# Battery_Protection.net
KiCad netlist of a schematic drawn in Altium Designer
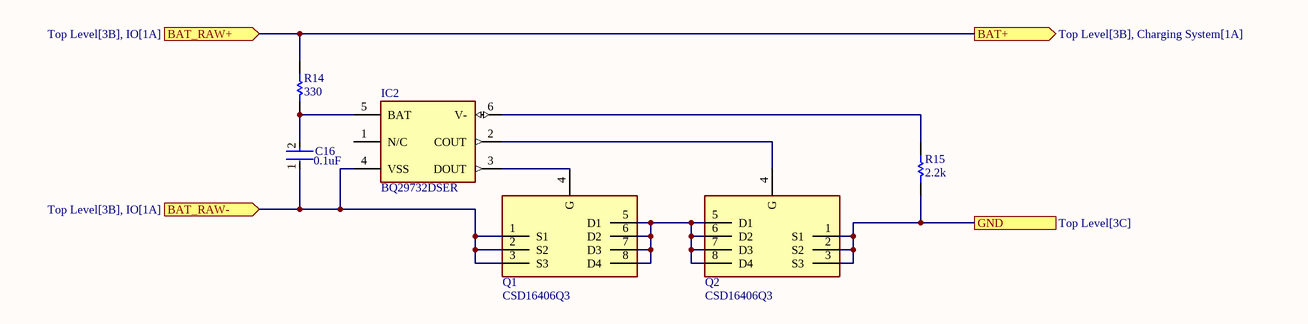
[diagram p0: Battery Protection.SchDoc]

(export (version "E")
  (design (tool "Eeschema 10.0.6"))
  (components
    (comp (ref "C16")
      (value "C1608X5R1A106K080AC")
      (footprint "FP-C1608-080-0_1-MFG")
      (description "Multilayer Ceramic Capacitors 10μF ±10% 10V X5R SMD 0603")
      (fields
        (field (name "VOLTAGE") "10V")
        (field (name "TOLERANCE") "10%")
        (field (name "CAPACITANCE") "0.1uF")
      )
      (libsource (lib "Altium Content Vault") (part "236180d848d6139a670b325ea6854c9"))
    )
    (comp (ref "IC2")
      (value "BQ29732DSER")
      (footprint "SON50P150X150X80-6N")
      (description "Integrated Circuit")
      (fields (field (name "MOUSER PART NUMBER") "595-BQ29732DSER"))
      (libsource (lib "Receiver_Library") (part "BQ29732DSER"))
    )
    (comp (ref "Q1")
      (value "CSD16406Q3")
      (footprint "DQG_VSON-CLIP")
      (description "MOSFET (N-Channel)")
      (fields (field (name "MOUSER PART NUMBER") "595-CSD16406Q3"))
      (libsource (lib "") (part "CSD16406Q3_1"))
    )
    (comp (ref "Q2")
      (value "CSD16406Q3")
      (footprint "DQG_VSON-CLIP")
      (description "MOSFET (N-Channel)")
      (fields (field (name "MOUSER PART NUMBER") "595-CSD16406Q3"))
      (libsource (lib "Receiver_Library") (part "CSD16406Q3"))
    )
    (comp (ref "R14")
      (value "330")
      (footprint "0603")
      (description "Thick Film Resistors - SMD 1/10Watt 2.1Kohms 1%")
      (fields (field (name "Comment") "CRCW06032K10FKEAC"))
      (libsource (lib "Receiver_Library") (part "CRCW06032K10FKEAC"))
    )
    (comp (ref "R15")
      (value "2.2k")
      (footprint "0603")
      (description "Thick Film Resistors - SMD 1/10Watt 2.1Kohms 1%")
      (fields (field (name "Comment") "CRCW06032K10FKEAC"))
      (libsource (lib "Receiver_Library") (part "CRCW06032K10FKEAC"))
    )
  )
  (nets
    (net (code "1") (name "/BAT+") (class "Default")
      (node (ref "R14") (pin "1") (pinfunction "1_1") (pintype "passive"))
    )
    (net (code "2") (name "/BAT_RAW-") (class "Default")
      (node (ref "C16") (pin "1") (pinfunction "1_1") (pintype "passive"))
      (node (ref "IC2") (pin "4") (pinfunction "VSS_4") (pintype "power_in"))
      (node (ref "Q1") (pin "1") (pinfunction "S1_1") (pintype "passive"))
      (node (ref "Q1") (pin "2") (pinfunction "S2_2") (pintype "passive"))
      (node (ref "Q1") (pin "3") (pinfunction "S3_3") (pintype "passive"))
    )
    (net (code "3") (name "/GND") (class "Default")
      (node (ref "Q2") (pin "1") (pinfunction "S1_1") (pintype "passive"))
      (node (ref "Q2") (pin "2") (pinfunction "S2_2") (pintype "passive"))
      (node (ref "Q2") (pin "3") (pinfunction "S3_3") (pintype "passive"))
      (node (ref "R15") (pin "2") (pinfunction "2_2") (pintype "passive"))
    )
    (net (code "4") (name "Net-(IC2-BAT)") (class "Default")
      (node (ref "C16") (pin "2") (pinfunction "2_2") (pintype "passive"))
      (node (ref "IC2") (pin "5") (pinfunction "BAT_5") (pintype "power_in"))
      (node (ref "R14") (pin "2") (pinfunction "2_2") (pintype "passive"))
    )
    (net (code "5") (name "Net-(IC2-COUT)") (class "Default")
      (node (ref "IC2") (pin "2") (pinfunction "COUT_2") (pintype "output"))
      (node (ref "Q2") (pin "4") (pinfunction "G_4") (pintype "passive"))
    )
    (net (code "6") (name "Net-(IC2-DOUT)") (class "Default")
      (node (ref "IC2") (pin "3") (pinfunction "DOUT_3") (pintype "output"))
      (node (ref "Q1") (pin "4") (pinfunction "G_4") (pintype "passive"))
    )
    (net (code "7") (name "Net-(IC2-V-)") (class "Default")
      (node (ref "IC2") (pin "6") (pinfunction "V-_6") (pintype "bidirectional"))
      (node (ref "R15") (pin "1") (pinfunction "1_1") (pintype "passive"))
    )
    (net (code "8") (name "Net-(Q1-D1)") (class "Default")
      (node (ref "Q1") (pin "5") (pinfunction "D1_5") (pintype "passive"))
      (node (ref "Q1") (pin "6") (pinfunction "D2_6") (pintype "passive"))
      (node (ref "Q1") (pin "7") (pinfunction "D3_7") (pintype "passive"))
      (node (ref "Q1") (pin "8") (pinfunction "D4_8") (pintype "passive"))
      (node (ref "Q2") (pin "5") (pinfunction "D1_5") (pintype "passive"))
      (node (ref "Q2") (pin "6") (pinfunction "D2_6") (pintype "passive"))
      (node (ref "Q2") (pin "7") (pinfunction "D3_7") (pintype "passive"))
      (node (ref "Q2") (pin "8") (pinfunction "D4_8") (pintype "passive"))
    )
    (net (code "9") (name "unconnected-(IC2-N{slash}C-Pad1)") (class "Default")
      (node (ref "IC2") (pin "1") (pinfunction "N/C_1") (pintype "passive"))
    )
  )
)
